# main_board.net
KiCad netlist of a schematic drawn in EAGLE
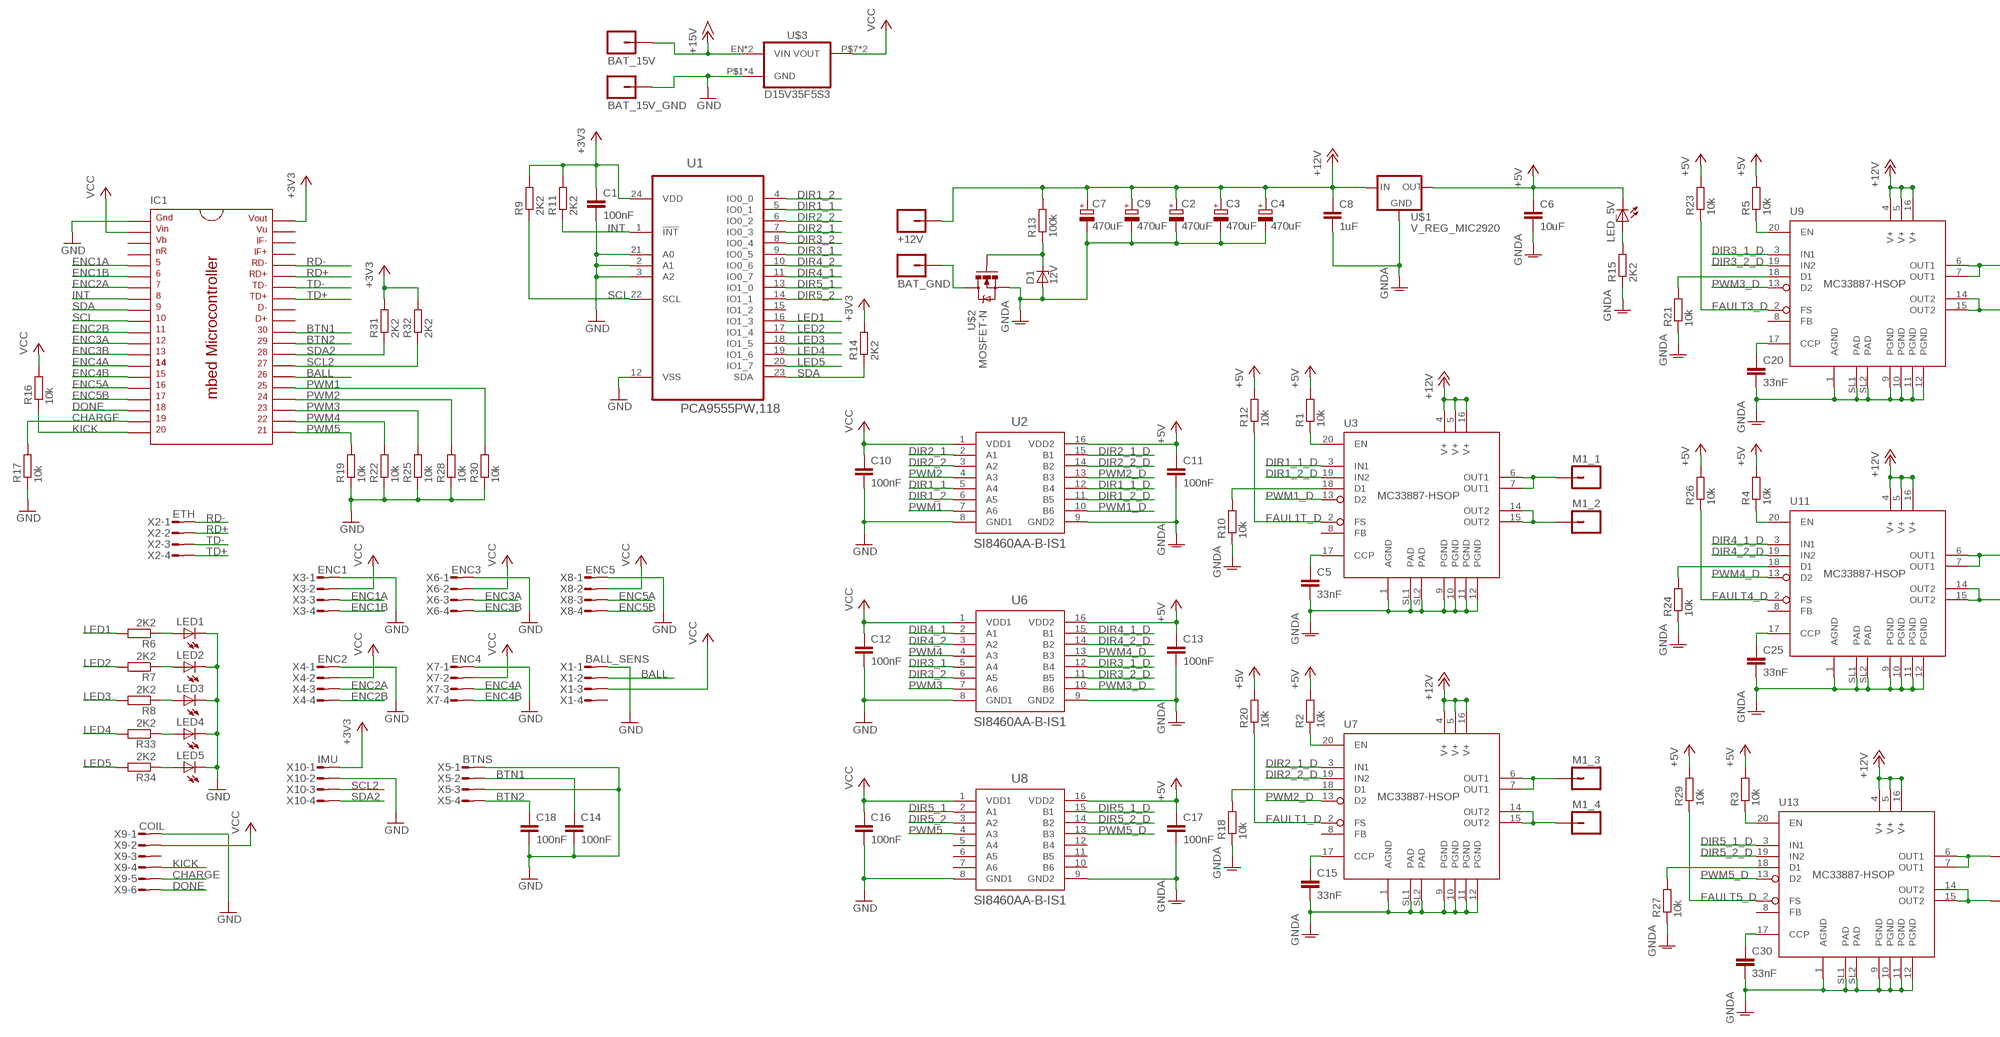
[diagram p0: schematic, sheet 1, part 1 of 2]
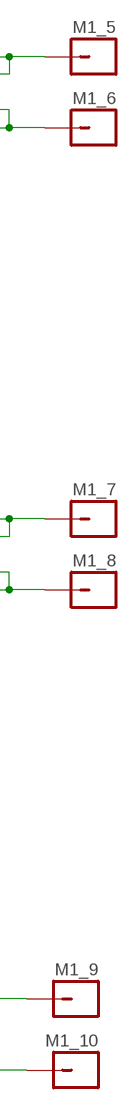
[diagram p1: schematic, sheet 1, part 2 of 2]

(export (version "E")
  (design (tool "Eeschema 10.0.6"))
  (components
    (comp (ref "+12V")
      (value "M01_PWR")
      (footprint "eagle-import:PWR_HOLE")
      (libsource (lib "eagle-import") (part "M01_PWR"))
    )
    (comp (ref "BAT_15V")
      (value "M01_WIRE")
      (footprint "eagle-import:WIRE_HOLE")
      (libsource (lib "eagle-import") (part "M01_WIRE"))
    )
    (comp (ref "BAT_15V_GND")
      (value "M01_WIRE")
      (footprint "eagle-import:WIRE_HOLE")
      (libsource (lib "eagle-import") (part "M01_WIRE"))
    )
    (comp (ref "BAT_GND")
      (value "M01_PWR")
      (footprint "eagle-import:PWR_HOLE")
      (libsource (lib "eagle-import") (part "M01_PWR"))
    )
    (comp (ref "C1")
      (value "100nF")
      (footprint "eagle-import:C0603K")
      (libsource (lib "eagle-import") (part "C-EUC0603K"))
    )
    (comp (ref "C2")
      (value "470uF")
      (footprint "eagle-import:E3,5-8")
      (libsource (lib "eagle-import") (part "CPOL-EUE3.5-8"))
    )
    (comp (ref "C3")
      (value "470uF")
      (footprint "eagle-import:E3,5-8")
      (libsource (lib "eagle-import") (part "CPOL-EUE3.5-8"))
    )
    (comp (ref "C4")
      (value "470uF")
      (footprint "eagle-import:E3,5-8")
      (libsource (lib "eagle-import") (part "CPOL-EUE3.5-8"))
    )
    (comp (ref "C5")
      (value "33nF")
      (footprint "eagle-import:C0603K")
      (libsource (lib "eagle-import") (part "C-EUC0603K"))
    )
    (comp (ref "C6")
      (value "10uF")
      (footprint "eagle-import:C1206K")
      (libsource (lib "eagle-import") (part "C-EUC1206K"))
    )
    (comp (ref "C7")
      (value "470uF")
      (footprint "eagle-import:E3,5-8")
      (libsource (lib "eagle-import") (part "CPOL-EUE3.5-8"))
    )
    (comp (ref "C8")
      (value "1uF")
      (footprint "eagle-import:C0603K")
      (libsource (lib "eagle-import") (part "C-EUC0603K"))
    )
    (comp (ref "C9")
      (value "470uF")
      (footprint "eagle-import:E3,5-8")
      (libsource (lib "eagle-import") (part "CPOL-EUE3.5-8"))
    )
    (comp (ref "C10")
      (value "100nF")
      (footprint "eagle-import:C0603K")
      (libsource (lib "eagle-import") (part "C-EUC0603K"))
    )
    (comp (ref "C11")
      (value "100nF")
      (footprint "eagle-import:C0603K")
      (libsource (lib "eagle-import") (part "C-EUC0603K"))
    )
    (comp (ref "C12")
      (value "100nF")
      (footprint "eagle-import:C0603K")
      (libsource (lib "eagle-import") (part "C-EUC0603K"))
    )
    (comp (ref "C13")
      (value "100nF")
      (footprint "eagle-import:C0603K")
      (libsource (lib "eagle-import") (part "C-EUC0603K"))
    )
    (comp (ref "C14")
      (value "100nF")
      (footprint "eagle-import:C0603K")
      (libsource (lib "eagle-import") (part "C-EUC0603K"))
    )
    (comp (ref "C15")
      (value "33nF")
      (footprint "eagle-import:C0603K")
      (libsource (lib "eagle-import") (part "C-EUC0603K"))
    )
    (comp (ref "C16")
      (value "100nF")
      (footprint "eagle-import:C0603K")
      (libsource (lib "eagle-import") (part "C-EUC0603K"))
    )
    (comp (ref "C17")
      (value "100nF")
      (footprint "eagle-import:C0603K")
      (libsource (lib "eagle-import") (part "C-EUC0603K"))
    )
    (comp (ref "C18")
      (value "100nF")
      (footprint "eagle-import:C0603K")
      (libsource (lib "eagle-import") (part "C-EUC0603K"))
    )
    (comp (ref "C20")
      (value "33nF")
      (footprint "eagle-import:C0603K")
      (libsource (lib "eagle-import") (part "C-EUC0603K"))
    )
    (comp (ref "C25")
      (value "33nF")
      (footprint "eagle-import:C0603K")
      (libsource (lib "eagle-import") (part "C-EUC0603K"))
    )
    (comp (ref "C30")
      (value "33nF")
      (footprint "eagle-import:C0603K")
      (libsource (lib "eagle-import") (part "C-EUC0603K"))
    )
    (comp (ref "D1")
      (value "12V")
      (footprint "eagle-import:SOD123")
      (libsource (lib "eagle-import") (part "ZENER-DIODESOD123"))
    )
    (comp (ref "IC1")
      (value "MBED_MICROCONTROLLER")
      (footprint "eagle-import:DIL40_0.9")
      (libsource (lib "eagle-import") (part "MBED_MICROCONTROLLER"))
    )
    (comp (ref "LED1")
      (value "LEDCHIP-LED0603")
      (footprint "eagle-import:CHIP-LED0603")
      (libsource (lib "eagle-import") (part "LEDCHIP-LED0603"))
    )
    (comp (ref "LED2")
      (value "LEDCHIP-LED0603")
      (footprint "eagle-import:CHIP-LED0603")
      (libsource (lib "eagle-import") (part "LEDCHIP-LED0603"))
    )
    (comp (ref "LED3")
      (value "LEDCHIP-LED0603")
      (footprint "eagle-import:CHIP-LED0603")
      (libsource (lib "eagle-import") (part "LEDCHIP-LED0603"))
    )
    (comp (ref "LED4")
      (value "LEDCHIP-LED0603")
      (footprint "eagle-import:CHIP-LED0603")
      (libsource (lib "eagle-import") (part "LEDCHIP-LED0603"))
    )
    (comp (ref "LED5")
      (value "LEDCHIP-LED0603")
      (footprint "eagle-import:CHIP-LED0603")
      (libsource (lib "eagle-import") (part "LEDCHIP-LED0603"))
    )
    (comp (ref "LED_5V")
      (value "LEDCHIP-LED0603")
      (footprint "eagle-import:CHIP-LED0603")
      (libsource (lib "eagle-import") (part "LEDCHIP-LED0603"))
    )
    (comp (ref "M1_1")
      (value "M01_WIRE")
      (footprint "eagle-import:WIRE_HOLE")
      (libsource (lib "eagle-import") (part "M01_WIRE"))
    )
    (comp (ref "M1_2")
      (value "M01_WIRE")
      (footprint "eagle-import:WIRE_HOLE")
      (libsource (lib "eagle-import") (part "M01_WIRE"))
    )
    (comp (ref "M1_3")
      (value "M01_WIRE")
      (footprint "eagle-import:WIRE_HOLE")
      (libsource (lib "eagle-import") (part "M01_WIRE"))
    )
    (comp (ref "M1_4")
      (value "M01_WIRE")
      (footprint "eagle-import:WIRE_HOLE")
      (libsource (lib "eagle-import") (part "M01_WIRE"))
    )
    (comp (ref "M1_5")
      (value "M01_WIRE")
      (footprint "eagle-import:WIRE_HOLE")
      (libsource (lib "eagle-import") (part "M01_WIRE"))
    )
    (comp (ref "M1_6")
      (value "M01_WIRE")
      (footprint "eagle-import:WIRE_HOLE")
      (libsource (lib "eagle-import") (part "M01_WIRE"))
    )
    (comp (ref "M1_7")
      (value "M01_WIRE")
      (footprint "eagle-import:WIRE_HOLE")
      (libsource (lib "eagle-import") (part "M01_WIRE"))
    )
    (comp (ref "M1_8")
      (value "M01_WIRE")
      (footprint "eagle-import:WIRE_HOLE")
      (libsource (lib "eagle-import") (part "M01_WIRE"))
    )
    (comp (ref "M1_9")
      (value "M01_WIRE")
      (footprint "eagle-import:WIRE_HOLE")
      (libsource (lib "eagle-import") (part "M01_WIRE"))
    )
    (comp (ref "M1_10")
      (value "M01_WIRE")
      (footprint "eagle-import:WIRE_HOLE")
      (libsource (lib "eagle-import") (part "M01_WIRE"))
    )
    (comp (ref "R1")
      (value "10k")
      (footprint "eagle-import:R0603")
      (libsource (lib "eagle-import") (part "R-EU_R0603"))
    )
    (comp (ref "R2")
      (value "10k")
      (footprint "eagle-import:R0603")
      (libsource (lib "eagle-import") (part "R-EU_R0603"))
    )
    (comp (ref "R3")
      (value "10k")
      (footprint "eagle-import:R0603")
      (libsource (lib "eagle-import") (part "R-EU_R0603"))
    )
    (comp (ref "R4")
      (value "10k")
      (footprint "eagle-import:R0603")
      (libsource (lib "eagle-import") (part "R-EU_R0603"))
    )
    (comp (ref "R5")
      (value "10k")
      (footprint "eagle-import:R0603")
      (libsource (lib "eagle-import") (part "R-EU_R0603"))
    )
    (comp (ref "R6")
      (value "2K2")
      (footprint "eagle-import:R0603")
      (libsource (lib "eagle-import") (part "R-EU_R0603"))
    )
    (comp (ref "R7")
      (value "2K2")
      (footprint "eagle-import:R0603")
      (libsource (lib "eagle-import") (part "R-EU_R0603"))
    )
    (comp (ref "R8")
      (value "2K2")
      (footprint "eagle-import:R0603")
      (libsource (lib "eagle-import") (part "R-EU_R0603"))
    )
    (comp (ref "R9")
      (value "2K2")
      (footprint "eagle-import:R0603")
      (libsource (lib "eagle-import") (part "R-EU_R0603"))
    )
    (comp (ref "R10")
      (value "10k")
      (footprint "eagle-import:R0603")
      (libsource (lib "eagle-import") (part "R-EU_R0603"))
    )
    (comp (ref "R11")
      (value "2K2")
      (footprint "eagle-import:R0603")
      (libsource (lib "eagle-import") (part "R-EU_R0603"))
    )
    (comp (ref "R12")
      (value "10k")
      (footprint "eagle-import:R0603")
      (libsource (lib "eagle-import") (part "R-EU_R0603"))
    )
    (comp (ref "R13")
      (value "100k")
      (footprint "eagle-import:R0603")
      (libsource (lib "eagle-import") (part "R-EU_R0603"))
    )
    (comp (ref "R14")
      (value "2K2")
      (footprint "eagle-import:R0603")
      (libsource (lib "eagle-import") (part "R-EU_R0603"))
    )
    (comp (ref "R15")
      (value "2K2")
      (footprint "eagle-import:R0603")
      (libsource (lib "eagle-import") (part "R-EU_R0603"))
    )
    (comp (ref "R16")
      (value "10k")
      (footprint "eagle-import:R0603")
      (libsource (lib "eagle-import") (part "R-EU_R0603"))
    )
    (comp (ref "R17")
      (value "10k")
      (footprint "eagle-import:R0603")
      (libsource (lib "eagle-import") (part "R-EU_R0603"))
    )
    (comp (ref "R18")
      (value "10k")
      (footprint "eagle-import:R0603")
      (libsource (lib "eagle-import") (part "R-EU_R0603"))
    )
    (comp (ref "R19")
      (value "10k")
      (footprint "eagle-import:R0603")
      (libsource (lib "eagle-import") (part "R-EU_R0603"))
    )
    (comp (ref "R20")
      (value "10k")
      (footprint "eagle-import:R0603")
      (libsource (lib "eagle-import") (part "R-EU_R0603"))
    )
    (comp (ref "R21")
      (value "10k")
      (footprint "eagle-import:R0603")
      (libsource (lib "eagle-import") (part "R-EU_R0603"))
    )
    (comp (ref "R22")
      (value "10k")
      (footprint "eagle-import:R0603")
      (libsource (lib "eagle-import") (part "R-EU_R0603"))
    )
    (comp (ref "R23")
      (value "10k")
      (footprint "eagle-import:R0603")
      (libsource (lib "eagle-import") (part "R-EU_R0603"))
    )
    (comp (ref "R24")
      (value "10k")
      (footprint "eagle-import:R0603")
      (libsource (lib "eagle-import") (part "R-EU_R0603"))
    )
    (comp (ref "R25")
      (value "10k")
      (footprint "eagle-import:R0603")
      (libsource (lib "eagle-import") (part "R-EU_R0603"))
    )
    (comp (ref "R26")
      (value "10k")
      (footprint "eagle-import:R0603")
      (libsource (lib "eagle-import") (part "R-EU_R0603"))
    )
    (comp (ref "R27")
      (value "10k")
      (footprint "eagle-import:R0603")
      (libsource (lib "eagle-import") (part "R-EU_R0603"))
    )
    (comp (ref "R28")
      (value "10k")
      (footprint "eagle-import:R0603")
      (libsource (lib "eagle-import") (part "R-EU_R0603"))
    )
    (comp (ref "R29")
      (value "10k")
      (footprint "eagle-import:R0603")
      (libsource (lib "eagle-import") (part "R-EU_R0603"))
    )
    (comp (ref "R30")
      (value "10k")
      (footprint "eagle-import:R0603")
      (libsource (lib "eagle-import") (part "R-EU_R0603"))
    )
    (comp (ref "R31")
      (value "2K2")
      (footprint "eagle-import:R0603")
      (libsource (lib "eagle-import") (part "R-EU_R0603"))
    )
    (comp (ref "R32")
      (value "2K2")
      (footprint "eagle-import:R0603")
      (libsource (lib "eagle-import") (part "R-EU_R0603"))
    )
    (comp (ref "R33")
      (value "2K2")
      (footprint "eagle-import:R0603")
      (libsource (lib "eagle-import") (part "R-EU_R0603"))
    )
    (comp (ref "R34")
      (value "2K2")
      (footprint "eagle-import:R0603")
      (libsource (lib "eagle-import") (part "R-EU_R0603"))
    )
    (comp (ref "U$1")
      (value "V_REG_MIC2920")
      (footprint "eagle-import:SOT223")
      (libsource (lib "eagle-import") (part "V_REG_MIC2920"))
    )
    (comp (ref "U$2")
      (value "MOSFET-N")
      (footprint "eagle-import:TO127P600X120-5N")
      (libsource (lib "eagle-import") (part "MOSFET-N-SOT669"))
    )
    (comp (ref "U$3")
      (value "D15V35F5S3")
      (footprint "eagle-import:D15V35F5S3")
      (libsource (lib "eagle-import") (part "D15V35F5S3"))
    )
    (comp (ref "U1")
      (value "PCA9555PW,118")
      (footprint "eagle-import:SOP65P640X110-24N")
      (libsource (lib "eagle-import") (part "PCA9555PW,118"))
    )
    (comp (ref "U2")
      (value "SI8460AA-B-IS1")
      (footprint "eagle-import:SOIC-16")
      (libsource (lib "eagle-import") (part "SI8460AA-B-IS1"))
    )
    (comp (ref "U3")
      (value "MC33887-HSOP")
      (footprint "eagle-import:HSOP")
      (libsource (lib "eagle-import") (part "MC33887-HSOP"))
    )
    (comp (ref "U6")
      (value "SI8460AA-B-IS1")
      (footprint "eagle-import:SOIC-16")
      (libsource (lib "eagle-import") (part "SI8460AA-B-IS1"))
    )
    (comp (ref "U7")
      (value "MC33887-HSOP")
      (footprint "eagle-import:HSOP")
      (libsource (lib "eagle-import") (part "MC33887-HSOP"))
    )
    (comp (ref "U8")
      (value "SI8460AA-B-IS1")
      (footprint "eagle-import:SOIC-16")
      (libsource (lib "eagle-import") (part "SI8460AA-B-IS1"))
    )
    (comp (ref "U9")
      (value "MC33887-HSOP")
      (footprint "eagle-import:HSOP")
      (libsource (lib "eagle-import") (part "MC33887-HSOP"))
    )
    (comp (ref "U11")
      (value "MC33887-HSOP")
      (footprint "eagle-import:HSOP")
      (libsource (lib "eagle-import") (part "MC33887-HSOP"))
    )
    (comp (ref "U13")
      (value "MC33887-HSOP")
      (footprint "eagle-import:HSOP")
      (libsource (lib "eagle-import") (part "MC33887-HSOP"))
    )
    (comp (ref "X1")
      (value "BALL_SENS")
      (footprint "eagle-import:MICROMATCH-4")
      (fields (field (name "MPN") "7-215464-4"))
      (libsource (lib "eagle-import") (part "MICROMATCH-4"))
    )
    (comp (ref "X2")
      (value "ETH")
      (footprint "eagle-import:MICROMATCH-4")
      (fields (field (name "MPN") "7-215464-4"))
      (libsource (lib "eagle-import") (part "MICROMATCH-4"))
    )
    (comp (ref "X3")
      (value "ENC1")
      (footprint "eagle-import:MICROMATCH-4")
      (fields (field (name "MPN") "7-215464-4"))
      (libsource (lib "eagle-import") (part "MICROMATCH-4"))
    )
    (comp (ref "X4")
      (value "ENC2")
      (footprint "eagle-import:MICROMATCH-4")
      (fields (field (name "MPN") "7-215464-4"))
      (libsource (lib "eagle-import") (part "MICROMATCH-4"))
    )
    (comp (ref "X5")
      (value "BTNS")
      (footprint "eagle-import:MICROMATCH-4")
      (fields (field (name "MPN") "7-215464-4"))
      (libsource (lib "eagle-import") (part "MICROMATCH-4"))
    )
    (comp (ref "X6")
      (value "ENC3")
      (footprint "eagle-import:MICROMATCH-4")
      (fields (field (name "MPN") "7-215464-4"))
      (libsource (lib "eagle-import") (part "MICROMATCH-4"))
    )
    (comp (ref "X7")
      (value "ENC4")
      (footprint "eagle-import:MICROMATCH-4")
      (fields (field (name "MPN") "7-215464-4"))
      (libsource (lib "eagle-import") (part "MICROMATCH-4"))
    )
    (comp (ref "X8")
      (value "ENC5")
      (footprint "eagle-import:MICROMATCH-4")
      (fields (field (name "MPN") "7-215464-4"))
      (libsource (lib "eagle-import") (part "MICROMATCH-4"))
    )
    (comp (ref "X9")
      (value "COIL")
      (footprint "eagle-import:MICROMATCH-6")
      (fields (field (name "MPN") "7-215464-6"))
      (libsource (lib "eagle-import") (part "MICROMATCH-6"))
    )
    (comp (ref "X10")
      (value "IMU")
      (footprint "eagle-import:MICROMATCH-4")
      (fields (field (name "MPN") "7-215464-4"))
      (libsource (lib "eagle-import") (part "MICROMATCH-4"))
    )
  )
  (nets
    (net (code "1") (name "+3V3") (class "Default")
      (node (ref "C1") (pin "1") (pinfunction "1_1") (pintype "passive"))
      (node (ref "IC1") (pin "40") (pinfunction "P$40_40") (pintype "bidirectional"))
      (node (ref "R11") (pin "2") (pinfunction "2_2") (pintype "passive"))
      (node (ref "R14") (pin "2") (pinfunction "2_2") (pintype "passive"))
      (node (ref "R31") (pin "2") (pinfunction "2_2") (pintype "passive"))
      (node (ref "R32") (pin "2") (pinfunction "2_2") (pintype "passive"))
      (node (ref "R9") (pin "2") (pinfunction "2_2") (pintype "passive"))
      (node (ref "U1") (pin "24") (pinfunction "VDD_24") (pintype "power_in"))
      (node (ref "X10") (pin "1") (pinfunction "S_1") (pintype "passive"))
    )
    (net (code "2") (name "+5V") (class "Default")
      (node (ref "C11") (pin "1") (pinfunction "1_1") (pintype "passive"))
      (node (ref "C13") (pin "1") (pinfunction "1_1") (pintype "passive"))
      (node (ref "C17") (pin "1") (pinfunction "1_1") (pintype "passive"))
      (node (ref "C6") (pin "1") (pinfunction "1_1") (pintype "passive"))
      (node (ref "LED_5V") (pin "C") (pinfunction "C_C") (pintype "passive"))
      (node (ref "R1") (pin "2") (pinfunction "2_2") (pintype "passive"))
      (node (ref "R12") (pin "2") (pinfunction "2_2") (pintype "passive"))
      (node (ref "R2") (pin "2") (pinfunction "2_2") (pintype "passive"))
      (node (ref "R20") (pin "2") (pinfunction "2_2") (pintype "passive"))
      (node (ref "R23") (pin "2") (pinfunction "2_2") (pintype "passive"))
      (node (ref "R26") (pin "2") (pinfunction "2_2") (pintype "passive"))
      (node (ref "R29") (pin "2") (pinfunction "2_2") (pintype "passive"))
      (node (ref "R3") (pin "2") (pinfunction "2_2") (pintype "passive"))
      (node (ref "R4") (pin "2") (pinfunction "2_2") (pintype "passive"))
      (node (ref "R5") (pin "2") (pinfunction "2_2") (pintype "passive"))
      (node (ref "U$1") (pin "3") (pinfunction "OUT_3") (pintype "output"))
      (node (ref "U2") (pin "16") (pinfunction "VDD2_16") (pintype "passive"))
      (node (ref "U6") (pin "16") (pinfunction "VDD2_16") (pintype "passive"))
      (node (ref "U8") (pin "16") (pinfunction "VDD2_16") (pintype "passive"))
    )
    (net (code "3") (name "+12V") (class "Default")
      (node (ref "+12V") (pin "P$1") (pinfunction "P$1_P$1") (pintype "bidirectional"))
      (node (ref "C2") (pin "+") (pinfunction "+_+") (pintype "passive"))
      (node (ref "C3") (pin "+") (pinfunction "+_+") (pintype "passive"))
      (node (ref "C4") (pin "+") (pinfunction "+_+") (pintype "passive"))
      (node (ref "C7") (pin "+") (pinfunction "+_+") (pintype "passive"))
      (node (ref "C8") (pin "1") (pinfunction "1_1") (pintype "passive"))
      (node (ref "C9") (pin "+") (pinfunction "+_+") (pintype "passive"))
      (node (ref "R13") (pin "2") (pinfunction "2_2") (pintype "passive"))
      (node (ref "U$1") (pin "1") (pinfunction "IN_1") (pintype "input"))
      (node (ref "U11") (pin "16") (pinfunction "V+_16") (pintype "power_in"))
      (node (ref "U11") (pin "4") (pinfunction "V+_4") (pintype "power_in"))
      (node (ref "U11") (pin "5") (pinfunction "V+_5") (pintype "power_in"))
      (node (ref "U13") (pin "16") (pinfunction "V+_16") (pintype "power_in"))
      (node (ref "U13") (pin "4") (pinfunction "V+_4") (pintype "power_in"))
      (node (ref "U13") (pin "5") (pinfunction "V+_5") (pintype "power_in"))
      (node (ref "U3") (pin "16") (pinfunction "V+_16") (pintype "power_in"))
      (node (ref "U3") (pin "4") (pinfunction "V+_4") (pintype "power_in"))
      (node (ref "U3") (pin "5") (pinfunction "V+_5") (pintype "power_in"))
      (node (ref "U7") (pin "16") (pinfunction "V+_16") (pintype "power_in"))
      (node (ref "U7") (pin "4") (pinfunction "V+_4") (pintype "power_in"))
      (node (ref "U7") (pin "5") (pinfunction "V+_5") (pintype "power_in"))
      (node (ref "U9") (pin "16") (pinfunction "V+_16") (pintype "power_in"))
      (node (ref "U9") (pin "4") (pinfunction "V+_4") (pintype "power_in"))
      (node (ref "U9") (pin "5") (pinfunction "V+_5") (pintype "power_in"))
    )
    (net (code "4") (name "+15V") (class "Default")
      (node (ref "BAT_15V") (pin "P$1") (pinfunction "P$1_P$1") (pintype "bidirectional"))
      (node (ref "U$3") (pin "EN") (pinfunction "VIN_EN") (pintype "power_in"))
      (node (ref "U$3") (pin "P$5") (pinfunction "VIN_P$5") (pintype "power_in"))
    )
    (net (code "5") (name "/BALL") (class "Default")
      (node (ref "IC1") (pin "26") (pinfunction "P$26_26") (pintype "bidirectional"))
      (node (ref "X1") (pin "2") (pinfunction "S_2") (pintype "passive"))
    )
    (net (code "6") (name "/BTN1") (class "Default")
      (node (ref "C14") (pin "1") (pinfunction "1_1") (pintype "passive"))
      (node (ref "IC1") (pin "30") (pinfunction "P$30_30") (pintype "bidirectional"))
      (node (ref "X5") (pin "2") (pinfunction "S_2") (pintype "passive"))
    )
    (net (code "7") (name "/BTN2") (class "Default")
      (node (ref "C18") (pin "1") (pinfunction "1_1") (pintype "passive"))
      (node (ref "IC1") (pin "29") (pinfunction "P$29_29") (pintype "bidirectional"))
      (node (ref "X5") (pin "4") (pinfunction "S_4") (pintype "passive"))
    )
    (net (code "8") (name "/CHARGE") (class "Default")
      (node (ref "IC1") (pin "19") (pinfunction "P$19_19") (pintype "bidirectional"))
      (node (ref "R17") (pin "2") (pinfunction "2_2") (pintype "passive"))
      (node (ref "X9") (pin "5") (pinfunction "S_5") (pintype "passive"))
    )
    (net (code "9") (name "/DIR1_1") (class "Default")
      (node (ref "U1") (pin "5") (pinfunction "IO0_1_5") (pintype "bidirectional"))
      (node (ref "U2") (pin "5") (pinfunction "A4_5") (pintype "input"))
    )
    (net (code "10") (name "/DIR1_1_D") (class "Default")
      (node (ref "U2") (pin "12") (pinfunction "B4_12") (pintype "output"))
      (node (ref "U3") (pin "3") (pinfunction "IN1_3") (pintype "input"))
    )
    (net (code "11") (name "/DIR1_2") (class "Default")
      (node (ref "U1") (pin "4") (pinfunction "IO0_0_4") (pintype "bidirectional"))
      (node (ref "U2") (pin "6") (pinfunction "A5_6") (pintype "input"))
    )
    (net (code "12") (name "/DIR1_2_D") (class "Default")
      (node (ref "U2") (pin "11") (pinfunction "B5_11") (pintype "output"))
      (node (ref "U3") (pin "19") (pinfunction "IN2_19") (pintype "input"))
    )
    (net (code "13") (name "/DIR2_1") (class "Default")
      (node (ref "U1") (pin "7") (pinfunction "IO0_3_7") (pintype "bidirectional"))
      (node (ref "U2") (pin "2") (pinfunction "A1_2") (pintype "input"))
    )
    (net (code "14") (name "/DIR2_1_D") (class "Default")
      (node (ref "U2") (pin "15") (pinfunction "B1_15") (pintype "output"))
      (node (ref "U7") (pin "3") (pinfunction "IN1_3") (pintype "input"))
    )
    (net (code "15") (name "/DIR2_2") (class "Default")
      (node (ref "U1") (pin "6") (pinfunction "IO0_2_6") (pintype "bidirectional"))
      (node (ref "U2") (pin "3") (pinfunction "A2_3") (pintype "input"))
    )
    (net (code "16") (name "/DIR2_2_D") (class "Default")
      (node (ref "U2") (pin "14") (pinfunction "B2_14") (pintype "output"))
      (node (ref "U7") (pin "19") (pinfunction "IN2_19") (pintype "input"))
    )
    (net (code "17") (name "/DIR3_1") (class "Default")
      (node (ref "U1") (pin "9") (pinfunction "IO0_5_9") (pintype "bidirectional"))
      (node (ref "U6") (pin "5") (pinfunction "A4_5") (pintype "input"))
    )
    (net (code "18") (name "/DIR3_1_D") (class "Default")
      (node (ref "U6") (pin "12") (pinfunction "B4_12") (pintype "output"))
      (node (ref "U9") (pin "3") (pinfunction "IN1_3") (pintype "input"))
    )
    (net (code "19") (name "/DIR3_2") (class "Default")
      (node (ref "U1") (pin "8") (pinfunction "IO0_4_8") (pintype "bidirectional"))
      (node (ref "U6") (pin "6") (pinfunction "A5_6") (pintype "input"))
    )
    (net (code "20") (name "/DIR3_2_D") (class "Default")
      (node (ref "U6") (pin "11") (pinfunction "B5_11") (pintype "output"))
      (node (ref "U9") (pin "19") (pinfunction "IN2_19") (pintype "input"))
    )
    (net (code "21") (name "/DIR4_1") (class "Default")
      (node (ref "U1") (pin "11") (pinfunction "IO0_7_11") (pintype "bidirectional"))
      (node (ref "U6") (pin "2") (pinfunction "A1_2") (pintype "input"))
    )
    (net (code "22") (name "/DIR4_1_D") (class "Default")
      (node (ref "U11") (pin "3") (pinfunction "IN1_3") (pintype "input"))
      (node (ref "U6") (pin "15") (pinfunction "B1_15") (pintype "output"))
    )
    (net (code "23") (name "/DIR4_2") (class "Default")
      (node (ref "U1") (pin "10") (pinfunction "IO0_6_10") (pintype "bidirectional"))
      (node (ref "U6") (pin "3") (pinfunction "A2_3") (pintype "input"))
    )
    (net (code "24") (name "/DIR4_2_D") (class "Default")
      (node (ref "U11") (pin "19") (pinfunction "IN2_19") (pintype "input"))
      (node (ref "U6") (pin "14") (pinfunction "B2_14") (pintype "output"))
    )
    (net (code "25") (name "/DIR5_1") (class "Default")
      (node (ref "U1") (pin "13") (pinfunction "IO1_0_13") (pintype "bidirectional"))
      (node (ref "U8") (pin "2") (pinfunction "A1_2") (pintype "input"))
    )
    (net (code "26") (name "/DIR5_1_D") (class "Default")
      (node (ref "U13") (pin "3") (pinfunction "IN1_3") (pintype "input"))
      (node (ref "U8") (pin "15") (pinfunction "B1_15") (pintype "output"))
    )
    (net (code "27") (name "/DIR5_2") (class "Default")
      (node (ref "U1") (pin "14") (pinfunction "IO1_1_14") (pintype "bidirectional"))
      (node (ref "U8") (pin "3") (pinfunction "A2_3") (pintype "input"))
    )
    (net (code "28") (name "/DIR5_2_D") (class "Default")
      (node (ref "U13") (pin "19") (pinfunction "IN2_19") (pintype "input"))
      (node (ref "U8") (pin "14") (pinfunction "B2_14") (pintype "output"))
    )
    (net (code "29") (name "/DONE") (class "Default")
      (node (ref "IC1") (pin "18") (pinfunction "P$18_18") (pintype "bidirectional"))
      (node (ref "X9") (pin "6") (pinfunction "S_6") (pintype "passive"))
    )
    (net (code "30") (name "/ENC1A") (class "Default")
      (node (ref "IC1") (pin "5") (pinfunction "P$5_5") (pintype "bidirectional"))
      (node (ref "X3") (pin "3") (pinfunction "S_3") (pintype "passive"))
    )
    (net (code "31") (name "/ENC1B") (class "Default")
      (node (ref "IC1") (pin "6") (pinfunction "P$6_6") (pintype "bidirectional"))
      (node (ref "X3") (pin "4") (pinfunction "S_4") (pintype "passive"))
    )
    (net (code "32") (name "/ENC2A") (class "Default")
      (node (ref "IC1") (pin "7") (pinfunction "P$7_7") (pintype "bidirectional"))
      (node (ref "X4") (pin "3") (pinfunction "S_3") (pintype "passive"))
    )
    (net (code "33") (name "/ENC2B") (class "Default")
      (node (ref "IC1") (pin "11") (pinfunction "P$11_11") (pintype "bidirectional"))
      (node (ref "X4") (pin "4") (pinfunction "S_4") (pintype "passive"))
    )
    (net (code "34") (name "/ENC3A") (class "Default")
      (node (ref "IC1") (pin "12") (pinfunction "P$12_12") (pintype "bidirectional"))
      (node (ref "X6") (pin "3") (pinfunction "S_3") (pintype "passive"))
    )
    (net (code "35") (name "/ENC3B") (class "Default")
      (node (ref "IC1") (pin "13") (pinfunction "P$13_13") (pintype "bidirectional"))
      (node (ref "X6") (pin "4") (pinfunction "S_4") (pintype "passive"))
    )
    (net (code "36") (name "/ENC4A") (class "Default")
      (node (ref "IC1") (pin "14") (pinfunction "P$14_14") (pintype "bidirectional"))
      (node (ref "X7") (pin "3") (pinfunction "S_3") (pintype "passive"))
    )
    (net (code "37") (name "/ENC4B") (class "Default")
      (node (ref "IC1") (pin "15") (pinfunction "P$15_15") (pintype "bidirectional"))
      (node (ref "X7") (pin "4") (pinfunction "S_4") (pintype "passive"))
    )
    (net (code "38") (name "/ENC5A") (class "Default")
      (node (ref "IC1") (pin "16") (pinfunction "P$16_16") (pintype "bidirectional"))
      (node (ref "X8") (pin "3") (pinfunction "S_3") (pintype "passive"))
    )
    (net (code "39") (name "/ENC5B") (class "Default")
      (node (ref "IC1") (pin "17") (pinfunction "P$17_17") (pintype "bidirectional"))
      (node (ref "X8") (pin "4") (pinfunction "S_4") (pintype "passive"))
    )
    (net (code "40") (name "/FAUL1T_D") (class "Default")
      (node (ref "R12") (pin "1") (pinfunction "1_1") (pintype "passive"))
      (node (ref "U3") (pin "2") (pinfunction "FS_2") (pintype "open_collector"))
    )
    (net (code "41") (name "/FAULT1_D") (class "Default")
      (node (ref "R20") (pin "1") (pinfunction "1_1") (pintype "passive"))
      (node (ref "U7") (pin "2") (pinfunction "FS_2") (pintype "open_collector"))
    )
    (net (code "42") (name "/FAULT3_D") (class "Default")
      (node (ref "R23") (pin "1") (pinfunction "1_1") (pintype "passive"))
      (node (ref "U9") (pin "2") (pinfunction "FS_2") (pintype "open_collector"))
    )
    (net (code "43") (name "/FAULT4_D") (class "Default")
      (node (ref "R26") (pin "1") (pinfunction "1_1") (pintype "passive"))
      (node (ref "U11") (pin "2") (pinfunction "FS_2") (pintype "open_collector"))
    )
    (net (code "44") (name "/FAULT5_D") (class "Default")
      (node (ref "R29") (pin "1") (pinfunction "1_1") (pintype "passive"))
      (node (ref "U13") (pin "2") (pinfunction "FS_2") (pintype "open_collector"))
    )
    (net (code "45") (name "/INT") (class "Default")
      (node (ref "IC1") (pin "8") (pinfunction "P$8_8") (pintype "bidirectional"))
      (node (ref "R11") (pin "1") (pinfunction "1_1") (pintype "passive"))
      (node (ref "U1") (pin "1") (pinfunction "~{INT}_1") (pintype "output"))
    )
    (net (code "46") (name "/KICK") (class "Default")
      (node (ref "IC1") (pin "20") (pinfunction "P$20_20") (pintype "bidirectional"))
      (node (ref "R16") (pin "1") (pinfunction "1_1") (pintype "passive"))
      (node (ref "X9") (pin "4") (pinfunction "S_4") (pintype "passive"))
    )
    (net (code "47") (name "/LED1") (class "Default")
      (node (ref "R6") (pin "2") (pinfunction "2_2") (pintype "passive"))
      (node (ref "U1") (pin "16") (pinfunction "IO1_3_16") (pintype "bidirectional"))
    )
    (net (code "48") (name "/LED2") (class "Default")
      (node (ref "R7") (pin "2") (pinfunction "2_2") (pintype "passive"))
      (node (ref "U1") (pin "17") (pinfunction "IO1_4_17") (pintype "bidirectional"))
    )
    (net (code "49") (name "/LED3") (class "Default")
      (node (ref "R8") (pin "2") (pinfunction "2_2") (pintype "passive"))
      (node (ref "U1") (pin "18") (pinfunction "IO1_5_18") (pintype "bidirectional"))
    )
    (net (code "50") (name "/LED4") (class "Default")
      (node (ref "R33") (pin "2") (pinfunction "2_2") (pintype "passive"))
      (node (ref "U1") (pin "19") (pinfunction "IO1_6_19") (pintype "bidirectional"))
    )
    (net (code "51") (name "/LED5") (class "Default")
      (node (ref "R34") (pin "2") (pinfunction "2_2") (pintype "passive"))
      (node (ref "U1") (pin "20") (pinfunction "IO1_7_20") (pintype "bidirectional"))
    )
    (net (code "52") (name "/PWM1") (class "Default")
      (node (ref "IC1") (pin "25") (pinfunction "P$25_25") (pintype "bidirectional"))
      (node (ref "R30") (pin "2") (pinfunction "2_2") (pintype "passive"))
      (node (ref "U2") (pin "7") (pinfunction "A6_7") (pintype "input"))
    )
    (net (code "53") (name "/PWM1_D") (class "Default")
      (node (ref "U2") (pin "10") (pinfunction "B6_10") (pintype "output"))
      (node (ref "U3") (pin "13") (pinfunction "D2_13") (pintype "input"))
    )
    (net (code "54") (name "/PWM2") (class "Default")
      (node (ref "IC1") (pin "24") (pinfunction "P$24_24") (pintype "bidirectional"))
      (node (ref "R28") (pin "2") (pinfunction "2_2") (pintype "passive"))
      (node (ref "U2") (pin "4") (pinfunction "A3_4") (pintype "input"))
    )
    (net (code "55") (name "/PWM2_D") (class "Default")
      (node (ref "U2") (pin "13") (pinfunction "B3_13") (pintype "output"))
      (node (ref "U7") (pin "13") (pinfunction "D2_13") (pintype "input"))
    )
    (net (code "56") (name "/PWM3") (class "Default")
      (node (ref "IC1") (pin "23") (pinfunction "P$23_23") (pintype "bidirectional"))
      (node (ref "R25") (pin "2") (pinfunction "2_2") (pintype "passive"))
      (node (ref "U6") (pin "7") (pinfunction "A6_7") (pintype "input"))
    )
    (net (code "57") (name "/PWM3_D") (class "Default")
      (node (ref "U6") (pin "10") (pinfunction "B6_10") (pintype "output"))
      (node (ref "U9") (pin "13") (pinfunction "D2_13") (pintype "input"))
    )
    (net (code "58") (name "/PWM4") (class "Default")
      (node (ref "IC1") (pin "22") (pinfunction "P$22_22") (pintype "bidirectional"))
      (node (ref "R22") (pin "2") (pinfunction "2_2") (pintype "passive"))
      (node (ref "U6") (pin "4") (pinfunction "A3_4") (pintype "input"))
    )
    (net (code "59") (name "/PWM4_D") (class "Default")
      (node (ref "U11") (pin "13") (pinfunction "D2_13") (pintype "input"))
      (node (ref "U6") (pin "13") (pinfunction "B3_13") (pintype "output"))
    )
    (net (code "60") (name "/PWM5") (class "Default")
      (node (ref "IC1") (pin "21") (pinfunction "P$21_21") (pintype "bidirectional"))
      (node (ref "R19") (pin "2") (pinfunction "2_2") (pintype "passive"))
      (node (ref "U8") (pin "4") (pinfunction "A3_4") (pintype "input"))
    )
    (net (code "61") (name "/PWM5_D") (class "Default")
      (node (ref "U13") (pin "13") (pinfunction "D2_13") (pintype "input"))
      (node (ref "U8") (pin "13") (pinfunction "B3_13") (pintype "output"))
    )
    (net (code "62") (name "/RD+") (class "Default")
      (node (ref "IC1") (pin "35") (pinfunction "P$35_35") (pintype "bidirectional"))
      (node (ref "X2") (pin "2") (pinfunction "S_2") (pintype "passive"))
    )
    (net (code "63") (name "/RD-") (class "Default")
      (node (ref "IC1") (pin "36") (pinfunction "P$36_36") (pintype "bidirectional"))
      (node (ref "X2") (pin "1") (pinfunction "S_1") (pintype "passive"))
    )
    (net (code "64") (name "/SCL") (class "Default")
      (node (ref "IC1") (pin "10") (pinfunction "P$10_10") (pintype "bidirectional"))
      (node (ref "R9") (pin "1") (pinfunction "1_1") (pintype "passive"))
      (node (ref "U1") (pin "22") (pinfunction "SCL_22") (pintype "input"))
    )
    (net (code "65") (name "/SCL2") (class "Default")
      (node (ref "IC1") (pin "27") (pinfunction "P$27_27") (pintype "bidirectional"))
      (node (ref "R32") (pin "1") (pinfunction "1_1") (pintype "passive"))
      (node (ref "X10") (pin "3") (pinfunction "S_3") (pintype "passive"))
    )
    (net (code "66") (name "/SDA") (class "Default")
      (node (ref "IC1") (pin "9") (pinfunction "P$9_9") (pintype "bidirectional"))
      (node (ref "R14") (pin "1") (pinfunction "1_1") (pintype "passive"))
      (node (ref "U1") (pin "23") (pinfunction "SDA_23") (pintype "bidirectional"))
    )
    (net (code "67") (name "/SDA2") (class "Default")
      (node (ref "IC1") (pin "28") (pinfunction "P$28_28") (pintype "bidirectional"))
      (node (ref "R31") (pin "1") (pinfunction "1_1") (pintype "passive"))
      (node (ref "X10") (pin "4") (pinfunction "S_4") (pintype "passive"))
    )
    (net (code "68") (name "/TD+") (class "Default")
      (node (ref "IC1") (pin "33") (pinfunction "P$33_33") (pintype "bidirectional"))
      (node (ref "X2") (pin "4") (pinfunction "S_4") (pintype "passive"))
    )
    (net (code "69") (name "/TD-") (class "Default")
      (node (ref "IC1") (pin "34") (pinfunction "P$34_34") (pintype "bidirectional"))
      (node (ref "X2") (pin "3") (pinfunction "S_3") (pintype "passive"))
    )
    (net (code "70") (name "GND") (class "Default")
      (node (ref "BAT_15V_GND") (pin "P$1") (pinfunction "P$1_P$1") (pintype "bidirectional"))
      (node (ref "C1") (pin "2") (pinfunction "2_2") (pintype "passive"))
      (node (ref "C10") (pin "2") (pinfunction "2_2") (pintype "passive"))
      (node (ref "C12") (pin "2") (pinfunction "2_2") (pintype "passive"))
      (node (ref "C14") (pin "2") (pinfunction "2_2") (pintype "passive"))
      (node (ref "C16") (pin "2") (pinfunction "2_2") (pintype "passive"))
      (node (ref "C18") (pin "2") (pinfunction "2_2") (pintype "passive"))
      (node (ref "IC1") (pin "1") (pinfunction "P$1_1") (pintype "bidirectional"))
      (node (ref "LED1") (pin "C") (pinfunction "C_C") (pintype "passive"))
      (node (ref "LED2") (pin "C") (pinfunction "C_C") (pintype "passive"))
      (node (ref "LED3") (pin "C") (pinfunction "C_C") (pintype "passive"))
      (node (ref "LED4") (pin "C") (pinfunction "C_C") (pintype "passive"))
      (node (ref "LED5") (pin "C") (pinfunction "C_C") (pintype "passive"))
      (node (ref "R17") (pin "1") (pinfunction "1_1") (pintype "passive"))
      (node (ref "R19") (pin "1") (pinfunction "1_1") (pintype "passive"))
      (node (ref "R22") (pin "1") (pinfunction "1_1") (pintype "passive"))
      (node (ref "R25") (pin "1") (pinfunction "1_1") (pintype "passive"))
      (node (ref "R28") (pin "1") (pinfunction "1_1") (pintype "passive"))
      (node (ref "R30") (pin "1") (pinfunction "1_1") (pintype "passive"))
      (node (ref "U$3") (pin "P$1") (pinfunction "GND_P$1") (pintype "power_in"))
      (node (ref "U$3") (pin "P$2") (pinfunction "GND_P$2") (pintype "power_in"))
      (node (ref "U$3") (pin "P$3") (pinfunction "GND_P$3") (pintype "power_in"))
      (node (ref "U$3") (pin "P$4") (pinfunction "GND_P$4") (pintype "power_in"))
      (node (ref "U1") (pin "12") (pinfunction "VSS_12") (pintype "power_in"))
      (node (ref "U1") (pin "2") (pinfunction "A1_2") (pintype "input"))
      (node (ref "U1") (pin "21") (pinfunction "A0_21") (pintype "input"))
      (node (ref "U1") (pin "3") (pinfunction "A2_3") (pintype "input"))
      (node (ref "U2") (pin "8") (pinfunction "GND1_8") (pintype "passive"))
      (node (ref "U6") (pin "8") (pinfunction "GND1_8") (pintype "passive"))
      (node (ref "U8") (pin "8") (pinfunction "GND1_8") (pintype "passive"))
      (node (ref "X1") (pin "1") (pinfunction "S_1") (pintype "passive"))
      (node (ref "X10") (pin "2") (pinfunction "S_2") (pintype "passive"))
      (node (ref "X3") (pin "1") (pinfunction "S_1") (pintype "passive"))
      (node (ref "X4") (pin "1") (pinfunction "S_1") (pintype "passive"))
      (node (ref "X5") (pin "1") (pinfunction "S_1") (pintype "passive"))
      (node (ref "X5") (pin "3") (pinfunction "S_3") (pintype "passive"))
      (node (ref "X6") (pin "1") (pinfunction "S_1") (pintype "passive"))
      (node (ref "X7") (pin "1") (pinfunction "S_1") (pintype "passive"))
      (node (ref "X8") (pin "1") (pinfunction "S_1") (pintype "passive"))
      (node (ref "X9") (pin "1") (pinfunction "S_1") (pintype "passive"))
    )
    (net (code "71") (name "GNDA") (class "Default")
      (node (ref "C11") (pin "2") (pinfunction "2_2") (pintype "passive"))
      (node (ref "C13") (pin "2") (pinfunction "2_2") (pintype "passive"))
      (node (ref "C15") (pin "2") (pinfunction "2_2") (pintype "passive"))
      (node (ref "C17") (pin "2") (pinfunction "2_2") (pintype "passive"))
      (node (ref "C2") (pin "-") (pinfunction "-_-") (pintype "passive"))
      (node (ref "C20") (pin "2") (pinfunction "2_2") (pintype "passive"))
      (node (ref "C25") (pin "2") (pinfunction "2_2") (pintype "passive"))
      (node (ref "C3") (pin "-") (pinfunction "-_-") (pintype "passive"))
      (node (ref "C30") (pin "2") (pinfunction "2_2") (pintype "passive"))
      (node (ref "C4") (pin "-") (pinfunction "-_-") (pintype "passive"))
      (node (ref "C5") (pin "2") (pinfunction "2_2") (pintype "passive"))
      (node (ref "C6") (pin "2") (pinfunction "2_2") (pintype "passive"))
      (node (ref "C7") (pin "-") (pinfunction "-_-") (pintype "passive"))
      (node (ref "C8") (pin "2") (pinfunction "2_2") (pintype "passive"))
      (node (ref "C9") (pin "-") (pinfunction "-_-") (pintype "passive"))
      (node (ref "D1") (pin "A") (pinfunction "A_A") (pintype "passive"))
      (node (ref "R10") (pin "1") (pinfunction "1_1") (pintype "passive"))
      (node (ref "R15") (pin "1") (pinfunction "1_1") (pintype "passive"))
      (node (ref "R18") (pin "1") (pinfunction "1_1") (pintype "passive"))
      (node (ref "R21") (pin "1") (pinfunction "1_1") (pintype "passive"))
      (node (ref "R24") (pin "1") (pinfunction "1_1") (pintype "passive"))
      (node (ref "R27") (pin "1") (pinfunction "1_1") (pintype "passive"))
      (node (ref "U$1") (pin "2") (pinfunction "GND_2") (pintype "input"))
      (node (ref "U$1") (pin "4") (pinfunction "GND_4") (pintype "input"))
      (node (ref "U$2") (pin "1") (pinfunction "S_1") (pintype "passive"))
      (node (ref "U$2") (pin "2") (pinfunction "S_2") (pintype "passive"))
      (node (ref "U$2") (pin "3") (pinfunction "S_3") (pintype "passive"))
      (node (ref "U11") (pin "1") (pinfunction "AGND_1") (pintype "power_in"))
      (node (ref "U11") (pin "10") (pinfunction "PGND_10") (pintype "power_in"))
      (node (ref "U11") (pin "11") (pinfunction "PGND_11") (pintype "power_in"))
      (node (ref "U11") (pin "12") (pinfunction "PGND_12") (pintype "power_in"))
      (node (ref "U11") (pin "9") (pinfunction "PGND_9") (pintype "power_in"))
      (node (ref "U11") (pin "SL1") (pinfunction "PAD_SL1") (pintype "passive"))
      (node (ref "U11") (pin "SL2") (pinfunction "PAD_SL2") (pintype "passive"))
      (node (ref "U13") (pin "1") (pinfunction "AGND_1") (pintype "power_in"))
      (node (ref "U13") (pin "10") (pinfunction "PGND_10") (pintype "power_in"))
      (node (ref "U13") (pin "11") (pinfunction "PGND_11") (pintype "power_in"))
      (node (ref "U13") (pin "12") (pinfunction "PGND_12") (pintype "power_in"))
      (node (ref "U13") (pin "9") (pinfunction "PGND_9") (pintype "power_in"))
      (node (ref "U13") (pin "SL1") (pinfunction "PAD_SL1") (pintype "passive"))
      (node (ref "U13") (pin "SL2") (pinfunction "PAD_SL2") (pintype "passive"))
      (node (ref "U2") (pin "9") (pinfunction "GND2_9") (pintype "passive"))
      (node (ref "U3") (pin "1") (pinfunction "AGND_1") (pintype "power_in"))
      (node (ref "U3") (pin "10") (pinfunction "PGND_10") (pintype "power_in"))
      (node (ref "U3") (pin "11") (pinfunction "PGND_11") (pintype "power_in"))
      (node (ref "U3") (pin "12") (pinfunction "PGND_12") (pintype "power_in"))
      (node (ref "U3") (pin "9") (pinfunction "PGND_9") (pintype "power_in"))
      (node (ref "U3") (pin "SL1") (pinfunction "PAD_SL1") (pintype "passive"))
      (node (ref "U3") (pin "SL2") (pinfunction "PAD_SL2") (pintype "passive"))
      (node (ref "U6") (pin "9") (pinfunction "GND2_9") (pintype "passive"))
      (node (ref "U7") (pin "1") (pinfunction "AGND_1") (pintype "power_in"))
      (node (ref "U7") (pin "10") (pinfunction "PGND_10") (pintype "power_in"))
      (node (ref "U7") (pin "11") (pinfunction "PGND_11") (pintype "power_in"))
      (node (ref "U7") (pin "12") (pinfunction "PGND_12") (pintype "power_in"))
      (node (ref "U7") (pin "9") (pinfunction "PGND_9") (pintype "power_in"))
      (node (ref "U7") (pin "SL1") (pinfunction "PAD_SL1") (pintype "passive"))
      (node (ref "U7") (pin "SL2") (pinfunction "PAD_SL2") (pintype "passive"))
      (node (ref "U8") (pin "9") (pinfunction "GND2_9") (pintype "passive"))
      (node (ref "U9") (pin "1") (pinfunction "AGND_1") (pintype "power_in"))
      (node (ref "U9") (pin "10") (pinfunction "PGND_10") (pintype "power_in"))
      (node (ref "U9") (pin "11") (pinfunction "PGND_11") (pintype "power_in"))
      (node (ref "U9") (pin "12") (pinfunction "PGND_12") (pintype "power_in"))
      (node (ref "U9") (pin "9") (pinfunction "PGND_9") (pintype "power_in"))
      (node (ref "U9") (pin "SL1") (pinfunction "PAD_SL1") (pintype "passive"))
      (node (ref "U9") (pin "SL2") (pinfunction "PAD_SL2") (pintype "passive"))
    )
    (net (code "72") (name "Net-(LED1-PadA)") (class "Default")
      (node (ref "LED1") (pin "A") (pinfunction "A_A") (pintype "passive"))
      (node (ref "R6") (pin "1") (pinfunction "1_1") (pintype "passive"))
    )
    (net (code "73") (name "Net-(LED2-PadA)") (class "Default")
      (node (ref "LED2") (pin "A") (pinfunction "A_A") (pintype "passive"))
      (node (ref "R7") (pin "1") (pinfunction "1_1") (pintype "passive"))
    )
    (net (code "74") (name "Net-(LED3-PadA)") (class "Default")
      (node (ref "LED3") (pin "A") (pinfunction "A_A") (pintype "passive"))
      (node (ref "R8") (pin "1") (pinfunction "1_1") (pintype "passive"))
    )
    (net (code "75") (name "Net-(LED4-PadA)") (class "Default")
      (node (ref "LED4") (pin "A") (pinfunction "A_A") (pintype "passive"))
      (node (ref "R33") (pin "1") (pinfunction "1_1") (pintype "passive"))
    )
    (net (code "76") (name "Net-(LED5-PadA)") (class "Default")
      (node (ref "LED5") (pin "A") (pinfunction "A_A") (pintype "passive"))
      (node (ref "R34") (pin "1") (pinfunction "1_1") (pintype "passive"))
    )
    (net (code "77") (name "Net-(LED_5V-PadA)") (class "Default")
      (node (ref "LED_5V") (pin "A") (pinfunction "A_A") (pintype "passive"))
      (node (ref "R15") (pin "2") (pinfunction "2_2") (pintype "passive"))
    )
    (net (code "78") (name "Net-(M1_1-PadP$1)") (class "Default")
      (node (ref "M1_1") (pin "P$1") (pinfunction "P$1_P$1") (pintype "bidirectional"))
      (node (ref "U3") (pin "6") (pinfunction "OUT1_6") (pintype "bidirectional"))
      (node (ref "U3") (pin "7") (pinfunction "OUT1_7") (pintype "bidirectional"))
    )
    (net (code "79") (name "Net-(M1_2-PadP$1)") (class "Default")
      (node (ref "M1_2") (pin "P$1") (pinfunction "P$1_P$1") (pintype "bidirectional"))
      (node (ref "U3") (pin "14") (pinfunction "OUT2_14") (pintype "bidirectional"))
      (node (ref "U3") (pin "15") (pinfunction "OUT2_15") (pintype "bidirectional"))
    )
    (net (code "80") (name "Net-(M1_3-PadP$1)") (class "Default")
      (node (ref "M1_3") (pin "P$1") (pinfunction "P$1_P$1") (pintype "bidirectional"))
      (node (ref "U7") (pin "6") (pinfunction "OUT1_6") (pintype "bidirectional"))
      (node (ref "U7") (pin "7") (pinfunction "OUT1_7") (pintype "bidirectional"))
    )
    (net (code "81") (name "Net-(M1_4-PadP$1)") (class "Default")
      (node (ref "M1_4") (pin "P$1") (pinfunction "P$1_P$1") (pintype "bidirectional"))
      (node (ref "U7") (pin "14") (pinfunction "OUT2_14") (pintype "bidirectional"))
      (node (ref "U7") (pin "15") (pinfunction "OUT2_15") (pintype "bidirectional"))
    )
    (net (code "82") (name "Net-(M1_5-PadP$1)") (class "Default")
      (node (ref "M1_5") (pin "P$1") (pinfunction "P$1_P$1") (pintype "bidirectional"))
      (node (ref "U9") (pin "6") (pinfunction "OUT1_6") (pintype "bidirectional"))
      (node (ref "U9") (pin "7") (pinfunction "OUT1_7") (pintype "bidirectional"))
    )
    (net (code "83") (name "Net-(M1_6-PadP$1)") (class "Default")
      (node (ref "M1_6") (pin "P$1") (pinfunction "P$1_P$1") (pintype "bidirectional"))
      (node (ref "U9") (pin "14") (pinfunction "OUT2_14") (pintype "bidirectional"))
      (node (ref "U9") (pin "15") (pinfunction "OUT2_15") (pintype "bidirectional"))
    )
    (net (code "84") (name "Net-(M1_7-PadP$1)") (class "Default")
      (node (ref "M1_7") (pin "P$1") (pinfunction "P$1_P$1") (pintype "bidirectional"))
      (node (ref "U11") (pin "6") (pinfunction "OUT1_6") (pintype "bidirectional"))
      (node (ref "U11") (pin "7") (pinfunction "OUT1_7") (pintype "bidirectional"))
    )
    (net (code "85") (name "Net-(M1_8-PadP$1)") (class "Default")
      (node (ref "M1_8") (pin "P$1") (pinfunction "P$1_P$1") (pintype "bidirectional"))
      (node (ref "U11") (pin "14") (pinfunction "OUT2_14") (pintype "bidirectional"))
      (node (ref "U11") (pin "15") (pinfunction "OUT2_15") (pintype "bidirectional"))
    )
    (net (code "86") (name "Net-(M1_9-PadP$1)") (class "Default")
      (node (ref "M1_9") (pin "P$1") (pinfunction "P$1_P$1") (pintype "bidirectional"))
      (node (ref "U13") (pin "6") (pinfunction "OUT1_6") (pintype "bidirectional"))
      (node (ref "U13") (pin "7") (pinfunction "OUT1_7") (pintype "bidirectional"))
    )
    (net (code "87") (name "Net-(M1_10-PadP$1)") (class "Default")
      (node (ref "M1_10") (pin "P$1") (pinfunction "P$1_P$1") (pintype "bidirectional"))
      (node (ref "U13") (pin "14") (pinfunction "OUT2_14") (pintype "bidirectional"))
      (node (ref "U13") (pin "15") (pinfunction "OUT2_15") (pintype "bidirectional"))
    )
    (net (code "88") (name "Net-(U$2-D)") (class "Default")
      (node (ref "BAT_GND") (pin "P$1") (pinfunction "P$1_P$1") (pintype "bidirectional"))
      (node (ref "U$2") (pin "5") (pinfunction "D_5") (pintype "passive"))
    )
    (net (code "89") (name "Net-(U$2-G)") (class "Default")
      (node (ref "D1") (pin "C") (pinfunction "C_C") (pintype "passive"))
      (node (ref "R13") (pin "1") (pinfunction "1_1") (pintype "passive"))
      (node (ref "U$2") (pin "4") (pinfunction "G_4") (pintype "passive"))
    )
    (net (code "90") (name "Net-(U3-CCP)") (class "Default")
      (node (ref "C5") (pin "1") (pinfunction "1_1") (pintype "passive"))
      (node (ref "U3") (pin "17") (pinfunction "CCP_17") (pintype "passive"))
    )
    (net (code "91") (name "Net-(U3-D1)") (class "Default")
      (node (ref "R10") (pin "2") (pinfunction "2_2") (pintype "passive"))
      (node (ref "U3") (pin "18") (pinfunction "D1_18") (pintype "input"))
    )
    (net (code "92") (name "Net-(U3-EN)") (class "Default")
      (node (ref "R1") (pin "1") (pinfunction "1_1") (pintype "passive"))
      (node (ref "U3") (pin "20") (pinfunction "EN_20") (pintype "input"))
    )
    (net (code "93") (name "Net-(U7-CCP)") (class "Default")
      (node (ref "C15") (pin "1") (pinfunction "1_1") (pintype "passive"))
      (node (ref "U7") (pin "17") (pinfunction "CCP_17") (pintype "passive"))
    )
    (net (code "94") (name "Net-(U7-D1)") (class "Default")
      (node (ref "R18") (pin "2") (pinfunction "2_2") (pintype "passive"))
      (node (ref "U7") (pin "18") (pinfunction "D1_18") (pintype "input"))
    )
    (net (code "95") (name "Net-(U7-EN)") (class "Default")
      (node (ref "R2") (pin "1") (pinfunction "1_1") (pintype "passive"))
      (node (ref "U7") (pin "20") (pinfunction "EN_20") (pintype "input"))
    )
    (net (code "96") (name "Net-(U9-CCP)") (class "Default")
      (node (ref "C20") (pin "1") (pinfunction "1_1") (pintype "passive"))
      (node (ref "U9") (pin "17") (pinfunction "CCP_17") (pintype "passive"))
    )
    (net (code "97") (name "Net-(U9-D1)") (class "Default")
      (node (ref "R21") (pin "2") (pinfunction "2_2") (pintype "passive"))
      (node (ref "U9") (pin "18") (pinfunction "D1_18") (pintype "input"))
    )
    (net (code "98") (name "Net-(U9-EN)") (class "Default")
      (node (ref "R5") (pin "1") (pinfunction "1_1") (pintype "passive"))
      (node (ref "U9") (pin "20") (pinfunction "EN_20") (pintype "input"))
    )
    (net (code "99") (name "Net-(U11-CCP)") (class "Default")
      (node (ref "C25") (pin "1") (pinfunction "1_1") (pintype "passive"))
      (node (ref "U11") (pin "17") (pinfunction "CCP_17") (pintype "passive"))
    )
    (net (code "100") (name "Net-(U11-D1)") (class "Default")
      (node (ref "R24") (pin "2") (pinfunction "2_2") (pintype "passive"))
      (node (ref "U11") (pin "18") (pinfunction "D1_18") (pintype "input"))
    )
    (net (code "101") (name "Net-(U11-EN)") (class "Default")
      (node (ref "R4") (pin "1") (pinfunction "1_1") (pintype "passive"))
      (node (ref "U11") (pin "20") (pinfunction "EN_20") (pintype "input"))
    )
    (net (code "102") (name "Net-(U13-CCP)") (class "Default")
      (node (ref "C30") (pin "1") (pinfunction "1_1") (pintype "passive"))
      (node (ref "U13") (pin "17") (pinfunction "CCP_17") (pintype "passive"))
    )
    (net (code "103") (name "Net-(U13-D1)") (class "Default")
      (node (ref "R27") (pin "2") (pinfunction "2_2") (pintype "passive"))
      (node (ref "U13") (pin "18") (pinfunction "D1_18") (pintype "input"))
    )
    (net (code "104") (name "Net-(U13-EN)") (class "Default")
      (node (ref "R3") (pin "1") (pinfunction "1_1") (pintype "passive"))
      (node (ref "U13") (pin "20") (pinfunction "EN_20") (pintype "input"))
    )
    (net (code "105") (name "VCC") (class "Default")
      (node (ref "C10") (pin "1") (pinfunction "1_1") (pintype "passive"))
      (node (ref "C12") (pin "1") (pinfunction "1_1") (pintype "passive"))
      (node (ref "C16") (pin "1") (pinfunction "1_1") (pintype "passive"))
      (node (ref "IC1") (pin "2") (pinfunction "P$2_2") (pintype "bidirectional"))
      (node (ref "R16") (pin "2") (pinfunction "2_2") (pintype "passive"))
      (node (ref "U$3") (pin "P$7") (pinfunction "VOUT_P$7") (pintype "power_in"))
      (node (ref "U$3") (pin "P$8") (pinfunction "VOUT_P$8") (pintype "power_in"))
      (node (ref "U2") (pin "1") (pinfunction "VDD1_1") (pintype "passive"))
      (node (ref "U6") (pin "1") (pinfunction "VDD1_1") (pintype "passive"))
      (node (ref "U8") (pin "1") (pinfunction "VDD1_1") (pintype "passive"))
      (node (ref "X1") (pin "3") (pinfunction "S_3") (pintype "passive"))
      (node (ref "X3") (pin "2") (pinfunction "S_2") (pintype "passive"))
      (node (ref "X4") (pin "2") (pinfunction "S_2") (pintype "passive"))
      (node (ref "X6") (pin "2") (pinfunction "S_2") (pintype "passive"))
      (node (ref "X7") (pin "2") (pinfunction "S_2") (pintype "passive"))
      (node (ref "X8") (pin "2") (pinfunction "S_2") (pintype "passive"))
      (node (ref "X9") (pin "2") (pinfunction "S_2") (pintype "passive"))
    )
    (net (code "106") (name "unconnected-(IC1-P$3-Pad3)") (class "Default")
      (node (ref "IC1") (pin "3") (pinfunction "P$3_3") (pintype "bidirectional"))
    )
    (net (code "107") (name "unconnected-(IC1-P$4-Pad4)") (class "Default")
      (node (ref "IC1") (pin "4") (pinfunction "P$4_4") (pintype "bidirectional"))
    )
    (net (code "108") (name "unconnected-(IC1-P$31-Pad31)") (class "Default")
      (node (ref "IC1") (pin "31") (pinfunction "P$31_31") (pintype "bidirectional"))
    )
    (net (code "109") (name "unconnected-(IC1-P$32-Pad32)") (class "Default")
      (node (ref "IC1") (pin "32") (pinfunction "P$32_32") (pintype "bidirectional"))
    )
    (net (code "110") (name "unconnected-(IC1-P$37-Pad37)") (class "Default")
      (node (ref "IC1") (pin "37") (pinfunction "P$37_37") (pintype "bidirectional"))
    )
    (net (code "111") (name "unconnected-(IC1-P$38-Pad38)") (class "Default")
      (node (ref "IC1") (pin "38") (pinfunction "P$38_38") (pintype "bidirectional"))
    )
    (net (code "112") (name "unconnected-(IC1-P$39-Pad39)") (class "Default")
      (node (ref "IC1") (pin "39") (pinfunction "P$39_39") (pintype "bidirectional"))
    )
    (net (code "113") (name "unconnected-(U1-IO1_2-Pad15)") (class "Default")
      (node (ref "U1") (pin "15") (pinfunction "IO1_2_15") (pintype "bidirectional"))
    )
    (net (code "114") (name "unconnected-(U3-FB-Pad8)") (class "Default")
      (node (ref "U3") (pin "8") (pinfunction "FB_8") (pintype "output"))
    )
    (net (code "115") (name "unconnected-(U7-FB-Pad8)") (class "Default")
      (node (ref "U7") (pin "8") (pinfunction "FB_8") (pintype "output"))
    )
    (net (code "116") (name "unconnected-(U8-A4-Pad5)") (class "Default")
      (node (ref "U8") (pin "5") (pinfunction "A4_5") (pintype "input"))
    )
    (net (code "117") (name "unconnected-(U8-A5-Pad6)") (class "Default")
      (node (ref "U8") (pin "6") (pinfunction "A5_6") (pintype "input"))
    )
    (net (code "118") (name "unconnected-(U8-A6-Pad7)") (class "Default")
      (node (ref "U8") (pin "7") (pinfunction "A6_7") (pintype "input"))
    )
    (net (code "119") (name "unconnected-(U8-B4-Pad12)") (class "Default")
      (node (ref "U8") (pin "12") (pinfunction "B4_12") (pintype "output"))
    )
    (net (code "120") (name "unconnected-(U8-B5-Pad11)") (class "Default")
      (node (ref "U8") (pin "11") (pinfunction "B5_11") (pintype "output"))
    )
    (net (code "121") (name "unconnected-(U8-B6-Pad10)") (class "Default")
      (node (ref "U8") (pin "10") (pinfunction "B6_10") (pintype "output"))
    )
    (net (code "122") (name "unconnected-(U9-FB-Pad8)") (class "Default")
      (node (ref "U9") (pin "8") (pinfunction "FB_8") (pintype "output"))
    )
    (net (code "123") (name "unconnected-(U11-FB-Pad8)") (class "Default")
      (node (ref "U11") (pin "8") (pinfunction "FB_8") (pintype "output"))
    )
    (net (code "124") (name "unconnected-(U13-FB-Pad8)") (class "Default")
      (node (ref "U13") (pin "8") (pinfunction "FB_8") (pintype "output"))
    )
    (net (code "125") (name "unconnected-(X1D-S-Pad4)") (class "Default")
      (node (ref "X1") (pin "4") (pinfunction "S_4") (pintype "passive"))
    )
    (net (code "126") (name "unconnected-(X9C-S-Pad3)") (class "Default")
      (node (ref "X9") (pin "3") (pinfunction "S_3") (pintype "passive"))
    )
  )
)
